# Power_Distribution_V1_1.net
KiCad netlist of a schematic drawn in EAGLE
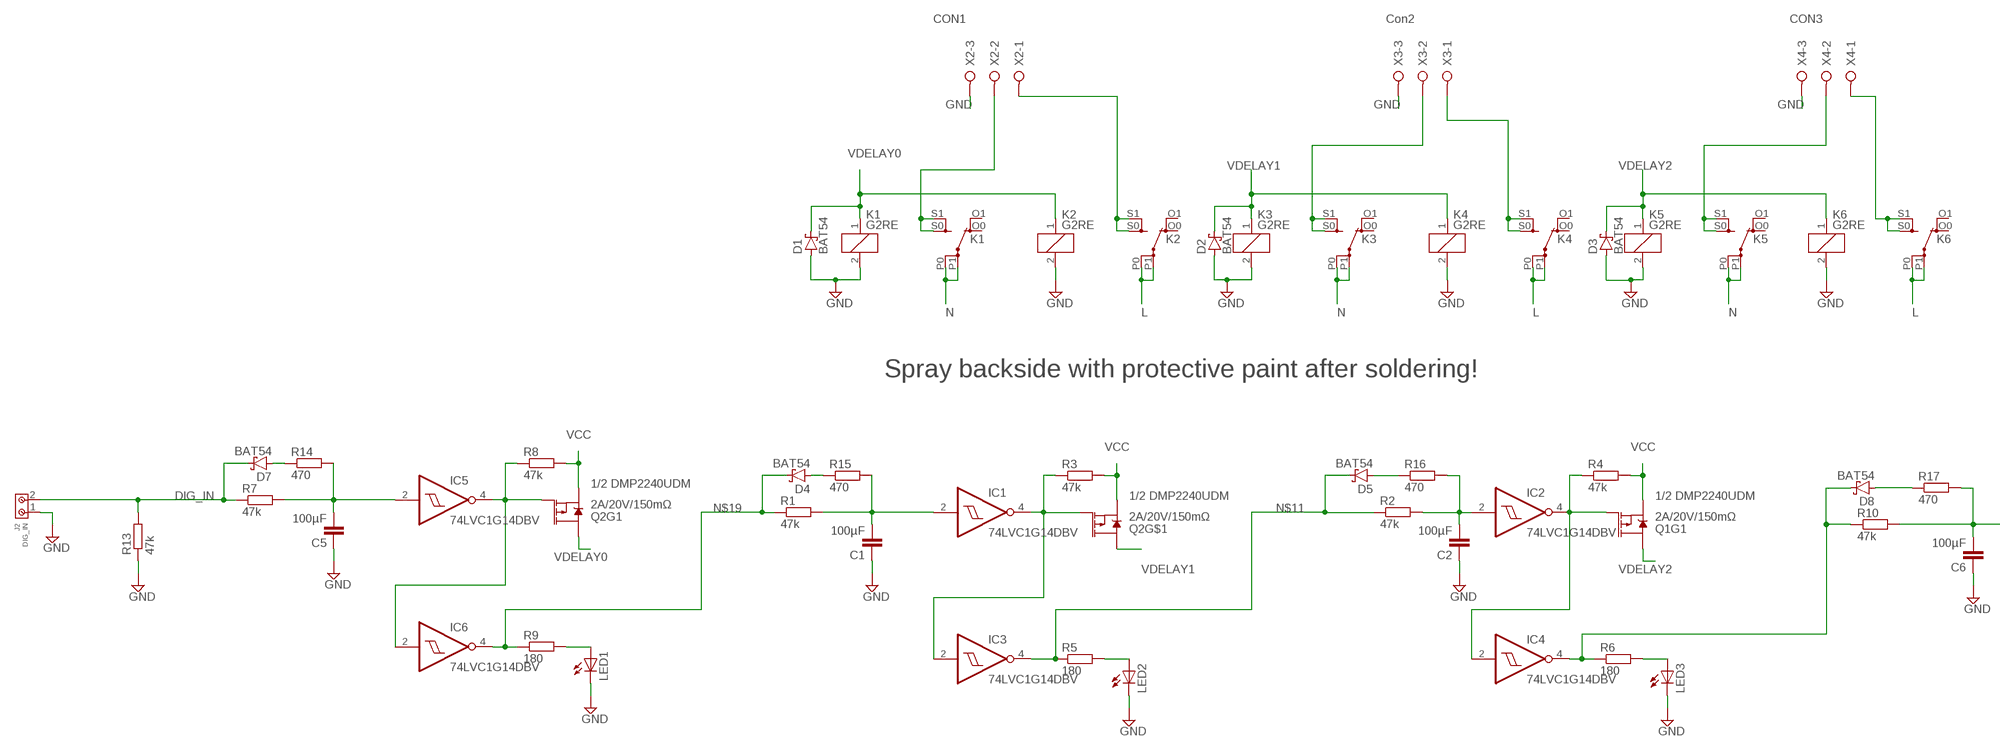
[diagram p0: schematic, sheet 1, part 1 of 2]
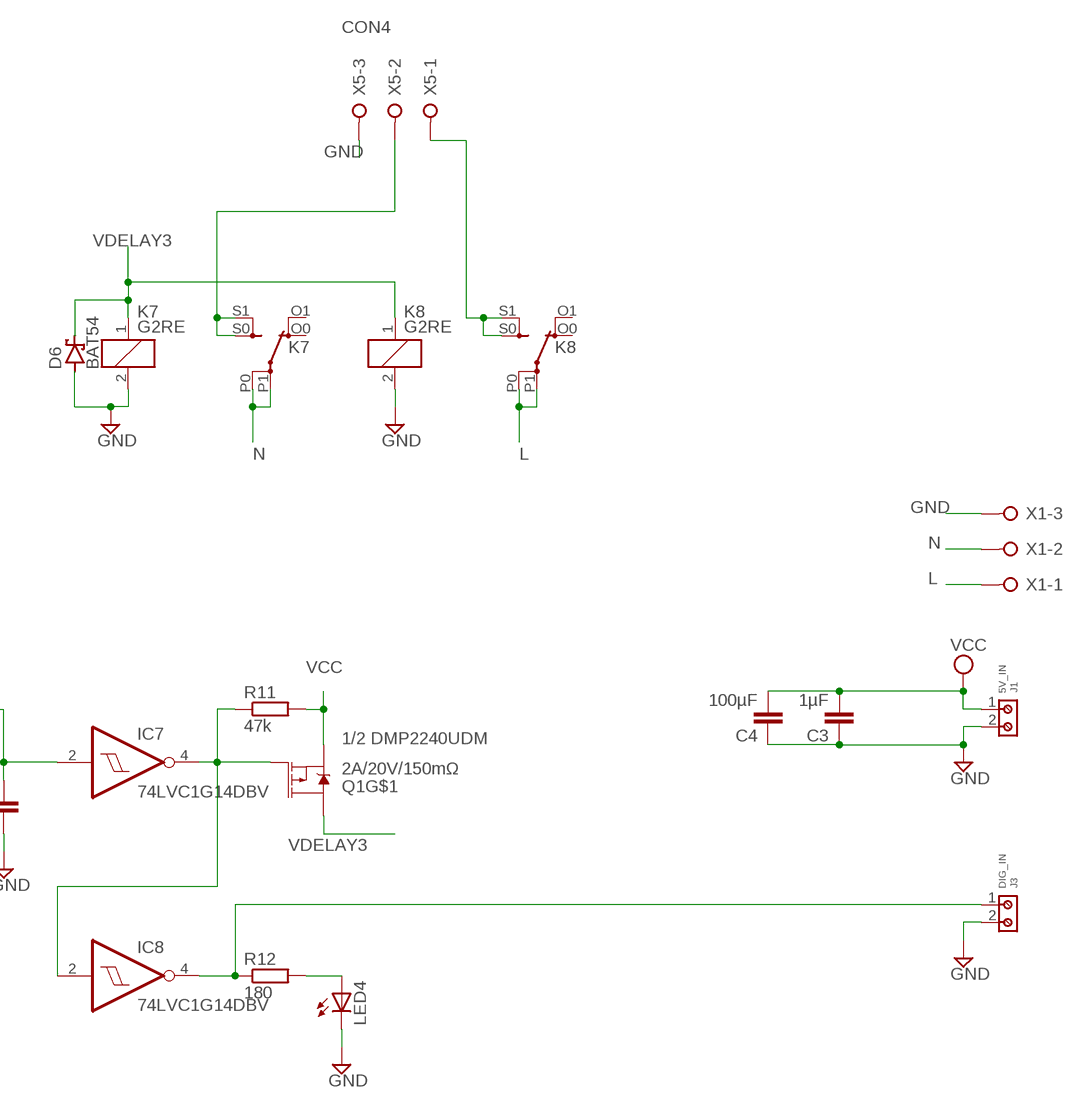
[diagram p1: schematic, sheet 1, part 2 of 2]

(export (version "E")
  (design (tool "Eeschema 10.0.6"))
  (components
    (comp (ref "C1")
      (value "100µF")
      (footprint "eagle-import:C1210")
      (libsource (lib "eagle-import") (part "C-EUC1210"))
    )
    (comp (ref "C2")
      (value "100µF")
      (footprint "eagle-import:C1210")
      (libsource (lib "eagle-import") (part "C-EUC1210"))
    )
    (comp (ref "C3")
      (value "1µF")
      (footprint "eagle-import:C1210")
      (libsource (lib "eagle-import") (part "C-EUC1210"))
    )
    (comp (ref "C4")
      (value "100µF")
      (footprint "eagle-import:C1210")
      (libsource (lib "eagle-import") (part "C-EUC1210"))
    )
    (comp (ref "C5")
      (value "100µF")
      (footprint "eagle-import:C1210")
      (libsource (lib "eagle-import") (part "C-EUC1210"))
    )
    (comp (ref "C6")
      (value "100µF")
      (footprint "eagle-import:C1210")
      (libsource (lib "eagle-import") (part "C-EUC1210"))
    )
    (comp (ref "D1")
      (value "BAT54")
      (footprint "eagle-import:SOT23")
      (libsource (lib "eagle-import") (part "BAT54"))
    )
    (comp (ref "D2")
      (value "BAT54")
      (footprint "eagle-import:SOT23")
      (libsource (lib "eagle-import") (part "BAT54"))
    )
    (comp (ref "D3")
      (value "BAT54")
      (footprint "eagle-import:SOT23")
      (libsource (lib "eagle-import") (part "BAT54"))
    )
    (comp (ref "D4")
      (value "BAT54")
      (footprint "eagle-import:SOT23")
      (libsource (lib "eagle-import") (part "BAT54"))
    )
    (comp (ref "D5")
      (value "BAT54")
      (footprint "eagle-import:SOT23")
      (libsource (lib "eagle-import") (part "BAT54"))
    )
    (comp (ref "D6")
      (value "BAT54")
      (footprint "eagle-import:SOT23")
      (libsource (lib "eagle-import") (part "BAT54"))
    )
    (comp (ref "D7")
      (value "BAT54")
      (footprint "eagle-import:SOT23")
      (libsource (lib "eagle-import") (part "BAT54"))
    )
    (comp (ref "D8")
      (value "BAT54")
      (footprint "eagle-import:SOT23")
      (libsource (lib "eagle-import") (part "BAT54"))
    )
    (comp (ref "IC1")
      (value "74LVC1G14DBV")
      (footprint "eagle-import:SOT23-5")
      (libsource (lib "eagle-import") (part "741G14DBVLVC"))
    )
    (comp (ref "IC2")
      (value "74LVC1G14DBV")
      (footprint "eagle-import:SOT23-5")
      (libsource (lib "eagle-import") (part "741G14DBVLVC"))
    )
    (comp (ref "IC3")
      (value "74LVC1G14DBV")
      (footprint "eagle-import:SOT23-5")
      (libsource (lib "eagle-import") (part "741G14DBVLVC"))
    )
    (comp (ref "IC4")
      (value "74LVC1G14DBV")
      (footprint "eagle-import:SOT23-5")
      (libsource (lib "eagle-import") (part "741G14DBVLVC"))
    )
    (comp (ref "IC5")
      (value "74LVC1G14DBV")
      (footprint "eagle-import:SOT23-5")
      (libsource (lib "eagle-import") (part "741G14DBVLVC"))
    )
    (comp (ref "IC6")
      (value "74LVC1G14DBV")
      (footprint "eagle-import:SOT23-5")
      (libsource (lib "eagle-import") (part "741G14DBVLVC"))
    )
    (comp (ref "IC7")
      (value "74LVC1G14DBV")
      (footprint "eagle-import:SOT23-5")
      (libsource (lib "eagle-import") (part "741G14DBVLVC"))
    )
    (comp (ref "IC8")
      (value "74LVC1G14DBV")
      (footprint "eagle-import:SOT23-5")
      (libsource (lib "eagle-import") (part "741G14DBVLVC"))
    )
    (comp (ref "J1")
      (value "5V_IN")
      (footprint "eagle-import:691210910002")
      (libsource (lib "eagle-import") (part "691210910002"))
    )
    (comp (ref "J2")
      (value "DIG_IN")
      (footprint "eagle-import:691210910002")
      (libsource (lib "eagle-import") (part "691210910002"))
    )
    (comp (ref "J3")
      (value "DIG_IN")
      (footprint "eagle-import:691210910002")
      (libsource (lib "eagle-import") (part "691210910002"))
    )
    (comp (ref "K1")
      (value "G2RE")
      (footprint "eagle-import:G2RE")
      (libsource (lib "eagle-import") (part "G2RE"))
    )
    (comp (ref "K2")
      (value "G2RE")
      (footprint "eagle-import:G2RE")
      (libsource (lib "eagle-import") (part "G2RE"))
    )
    (comp (ref "K3")
      (value "G2RE")
      (footprint "eagle-import:G2RE")
      (libsource (lib "eagle-import") (part "G2RE"))
    )
    (comp (ref "K4")
      (value "G2RE")
      (footprint "eagle-import:G2RE")
      (libsource (lib "eagle-import") (part "G2RE"))
    )
    (comp (ref "K5")
      (value "G2RE")
      (footprint "eagle-import:G2RE")
      (libsource (lib "eagle-import") (part "G2RE"))
    )
    (comp (ref "K6")
      (value "G2RE")
      (footprint "eagle-import:G2RE")
      (libsource (lib "eagle-import") (part "G2RE"))
    )
    (comp (ref "K7")
      (value "G2RE")
      (footprint "eagle-import:G2RE")
      (libsource (lib "eagle-import") (part "G2RE"))
    )
    (comp (ref "K8")
      (value "G2RE")
      (footprint "eagle-import:G2RE")
      (libsource (lib "eagle-import") (part "G2RE"))
    )
    (comp (ref "LED1")
      (value "LED3MM")
      (footprint "eagle-import:LED3MM")
      (libsource (lib "eagle-import") (part "LED3MM"))
    )
    (comp (ref "LED2")
      (value "LED3MM")
      (footprint "eagle-import:LED3MM")
      (libsource (lib "eagle-import") (part "LED3MM"))
    )
    (comp (ref "LED3")
      (value "LED3MM")
      (footprint "eagle-import:LED3MM")
      (libsource (lib "eagle-import") (part "LED3MM"))
    )
    (comp (ref "LED4")
      (value "LED3MM")
      (footprint "eagle-import:LED3MM")
      (libsource (lib "eagle-import") (part "LED3MM"))
    )
    (comp (ref "Q1")
      (value "2A/20V/150mΩ")
      (footprint "eagle-import:SOT26")
      (libsource (lib "eagle-import") (part "MOSFET_PCH_DUAL-DMP2240UDM"))
    )
    (comp (ref "Q2")
      (value "2A/20V/150mΩ")
      (footprint "eagle-import:SOT26")
      (libsource (lib "eagle-import") (part "MOSFET_PCH_DUAL-DMP2240UDM"))
    )
    (comp (ref "R1")
      (value "47k")
      (footprint "eagle-import:R0805")
      (libsource (lib "eagle-import") (part "R-EU_R0805"))
    )
    (comp (ref "R2")
      (value "47k")
      (footprint "eagle-import:R0805")
      (libsource (lib "eagle-import") (part "R-EU_R0805"))
    )
    (comp (ref "R3")
      (value "47k")
      (footprint "eagle-import:R0805")
      (libsource (lib "eagle-import") (part "R-EU_R0805"))
    )
    (comp (ref "R4")
      (value "47k")
      (footprint "eagle-import:R0805")
      (libsource (lib "eagle-import") (part "R-EU_R0805"))
    )
    (comp (ref "R5")
      (value "180")
      (footprint "eagle-import:R0805")
      (libsource (lib "eagle-import") (part "R-EU_R0805"))
    )
    (comp (ref "R6")
      (value "180")
      (footprint "eagle-import:R0805")
      (libsource (lib "eagle-import") (part "R-EU_R0805"))
    )
    (comp (ref "R7")
      (value "47k")
      (footprint "eagle-import:R0805")
      (libsource (lib "eagle-import") (part "R-EU_R0805"))
    )
    (comp (ref "R8")
      (value "47k")
      (footprint "eagle-import:R0805")
      (libsource (lib "eagle-import") (part "R-EU_R0805"))
    )
    (comp (ref "R9")
      (value "180")
      (footprint "eagle-import:R0805")
      (libsource (lib "eagle-import") (part "R-EU_R0805"))
    )
    (comp (ref "R10")
      (value "47k")
      (footprint "eagle-import:R0805")
      (libsource (lib "eagle-import") (part "R-EU_R0805"))
    )
    (comp (ref "R11")
      (value "47k")
      (footprint "eagle-import:R0805")
      (libsource (lib "eagle-import") (part "R-EU_R0805"))
    )
    (comp (ref "R12")
      (value "180")
      (footprint "eagle-import:R0805")
      (libsource (lib "eagle-import") (part "R-EU_R0805"))
    )
    (comp (ref "R13")
      (value "47k")
      (footprint "eagle-import:R0805")
      (libsource (lib "eagle-import") (part "R-EU_R0805"))
    )
    (comp (ref "R14")
      (value "470")
      (footprint "eagle-import:R0805")
      (libsource (lib "eagle-import") (part "R-EU_R0805"))
    )
    (comp (ref "R15")
      (value "470")
      (footprint "eagle-import:R0805")
      (libsource (lib "eagle-import") (part "R-EU_R0805"))
    )
    (comp (ref "R16")
      (value "470")
      (footprint "eagle-import:R0805")
      (libsource (lib "eagle-import") (part "R-EU_R0805"))
    )
    (comp (ref "R17")
      (value "470")
      (footprint "eagle-import:R0805")
      (libsource (lib "eagle-import") (part "R-EU_R0805"))
    )
    (comp (ref "X1")
      (value "W237-3E")
      (footprint "eagle-import:W237-3E")
      (libsource (lib "eagle-import") (part "W237-3E"))
    )
    (comp (ref "X2")
      (value "W237-3E")
      (footprint "eagle-import:W237-3E")
      (libsource (lib "eagle-import") (part "W237-3E"))
    )
    (comp (ref "X3")
      (value "W237-3E")
      (footprint "eagle-import:W237-3E")
      (libsource (lib "eagle-import") (part "W237-3E"))
    )
    (comp (ref "X4")
      (value "W237-3E")
      (footprint "eagle-import:W237-3E")
      (libsource (lib "eagle-import") (part "W237-3E"))
    )
    (comp (ref "X5")
      (value "W237-3E")
      (footprint "eagle-import:W237-3E")
      (libsource (lib "eagle-import") (part "W237-3E"))
    )
  )
  (nets
    (net (code "1") (name "/DIG_IN") (class "Default")
      (node (ref "D7") (pin "3") (pinfunction "C_3") (pintype "passive"))
      (node (ref "J2") (pin "2") (pinfunction "2_2") (pintype "passive"))
      (node (ref "R13") (pin "2") (pinfunction "2_2") (pintype "passive"))
      (node (ref "R7") (pin "1") (pinfunction "1_1") (pintype "passive"))
    )
    (net (code "2") (name "/L") (class "Default")
      (node (ref "K2") (pin "P0") (pinfunction "P_P0") (pintype "passive"))
      (node (ref "K2") (pin "P1") (pinfunction "P_P1") (pintype "passive"))
      (node (ref "K4") (pin "P0") (pinfunction "P_P0") (pintype "passive"))
      (node (ref "K4") (pin "P1") (pinfunction "P_P1") (pintype "passive"))
      (node (ref "K6") (pin "P0") (pinfunction "P_P0") (pintype "passive"))
      (node (ref "K6") (pin "P1") (pinfunction "P_P1") (pintype "passive"))
      (node (ref "K8") (pin "P0") (pinfunction "P_P0") (pintype "passive"))
      (node (ref "K8") (pin "P1") (pinfunction "P_P1") (pintype "passive"))
      (node (ref "X1") (pin "1") (pinfunction "KL_1") (pintype "passive"))
    )
    (net (code "3") (name "/N") (class "Default")
      (node (ref "K1") (pin "P0") (pinfunction "P_P0") (pintype "passive"))
      (node (ref "K1") (pin "P1") (pinfunction "P_P1") (pintype "passive"))
      (node (ref "K3") (pin "P0") (pinfunction "P_P0") (pintype "passive"))
      (node (ref "K3") (pin "P1") (pinfunction "P_P1") (pintype "passive"))
      (node (ref "K5") (pin "P0") (pinfunction "P_P0") (pintype "passive"))
      (node (ref "K5") (pin "P1") (pinfunction "P_P1") (pintype "passive"))
      (node (ref "K7") (pin "P0") (pinfunction "P_P0") (pintype "passive"))
      (node (ref "K7") (pin "P1") (pinfunction "P_P1") (pintype "passive"))
      (node (ref "X1") (pin "2") (pinfunction "KL_2") (pintype "passive"))
    )
    (net (code "4") (name "/N$11") (class "Default")
      (node (ref "D5") (pin "3") (pinfunction "C_3") (pintype "passive"))
      (node (ref "IC3") (pin "4") (pinfunction "O_4") (pintype "output"))
      (node (ref "R2") (pin "1") (pinfunction "1_1") (pintype "passive"))
      (node (ref "R5") (pin "1") (pinfunction "1_1") (pintype "passive"))
    )
    (net (code "5") (name "/N$19") (class "Default")
      (node (ref "D4") (pin "3") (pinfunction "C_3") (pintype "passive"))
      (node (ref "IC6") (pin "4") (pinfunction "O_4") (pintype "output"))
      (node (ref "R1") (pin "1") (pinfunction "1_1") (pintype "passive"))
      (node (ref "R9") (pin "1") (pinfunction "1_1") (pintype "passive"))
    )
    (net (code "6") (name "/VDELAY0") (class "Default")
      (node (ref "D1") (pin "3") (pinfunction "C_3") (pintype "passive"))
      (node (ref "K1") (pin "1") (pinfunction "1_1") (pintype "passive"))
      (node (ref "K2") (pin "1") (pinfunction "1_1") (pintype "passive"))
      (node (ref "Q2") (pin "D1") (pinfunction "D_D1") (pintype "bidirectional"))
    )
    (net (code "7") (name "/VDELAY1") (class "Default")
      (node (ref "D2") (pin "3") (pinfunction "C_3") (pintype "passive"))
      (node (ref "K3") (pin "1") (pinfunction "1_1") (pintype "passive"))
      (node (ref "K4") (pin "1") (pinfunction "1_1") (pintype "passive"))
      (node (ref "Q2") (pin "D2") (pinfunction "D_D2") (pintype "bidirectional"))
    )
    (net (code "8") (name "/VDELAY2") (class "Default")
      (node (ref "D3") (pin "3") (pinfunction "C_3") (pintype "passive"))
      (node (ref "K5") (pin "1") (pinfunction "1_1") (pintype "passive"))
      (node (ref "K6") (pin "1") (pinfunction "1_1") (pintype "passive"))
      (node (ref "Q1") (pin "D1") (pinfunction "D_D1") (pintype "bidirectional"))
    )
    (net (code "9") (name "/VDELAY3") (class "Default")
      (node (ref "D6") (pin "3") (pinfunction "C_3") (pintype "passive"))
      (node (ref "K7") (pin "1") (pinfunction "1_1") (pintype "passive"))
      (node (ref "K8") (pin "1") (pinfunction "1_1") (pintype "passive"))
      (node (ref "Q1") (pin "D2") (pinfunction "D_D2") (pintype "bidirectional"))
    )
    (net (code "10") (name "GND") (class "Default")
      (node (ref "C1") (pin "1") (pinfunction "1_1") (pintype "passive"))
      (node (ref "C2") (pin "1") (pinfunction "1_1") (pintype "passive"))
      (node (ref "C3") (pin "1") (pinfunction "1_1") (pintype "passive"))
      (node (ref "C4") (pin "1") (pinfunction "1_1") (pintype "passive"))
      (node (ref "C5") (pin "1") (pinfunction "1_1") (pintype "passive"))
      (node (ref "C6") (pin "1") (pinfunction "1_1") (pintype "passive"))
      (node (ref "D1") (pin "1") (pinfunction "A_1") (pintype "passive"))
      (node (ref "D2") (pin "1") (pinfunction "A_1") (pintype "passive"))
      (node (ref "D3") (pin "1") (pinfunction "A_1") (pintype "passive"))
      (node (ref "D6") (pin "1") (pinfunction "A_1") (pintype "passive"))
      (node (ref "J1") (pin "2") (pinfunction "2_2") (pintype "passive"))
      (node (ref "J2") (pin "1") (pinfunction "1_1") (pintype "passive"))
      (node (ref "J3") (pin "2") (pinfunction "2_2") (pintype "passive"))
      (node (ref "K1") (pin "2") (pinfunction "2_2") (pintype "passive"))
      (node (ref "K2") (pin "2") (pinfunction "2_2") (pintype "passive"))
      (node (ref "K3") (pin "2") (pinfunction "2_2") (pintype "passive"))
      (node (ref "K4") (pin "2") (pinfunction "2_2") (pintype "passive"))
      (node (ref "K5") (pin "2") (pinfunction "2_2") (pintype "passive"))
      (node (ref "K6") (pin "2") (pinfunction "2_2") (pintype "passive"))
      (node (ref "K7") (pin "2") (pinfunction "2_2") (pintype "passive"))
      (node (ref "K8") (pin "2") (pinfunction "2_2") (pintype "passive"))
      (node (ref "LED1") (pin "K") (pinfunction "C_K") (pintype "passive"))
      (node (ref "LED2") (pin "K") (pinfunction "C_K") (pintype "passive"))
      (node (ref "LED3") (pin "K") (pinfunction "C_K") (pintype "passive"))
      (node (ref "LED4") (pin "K") (pinfunction "C_K") (pintype "passive"))
      (node (ref "R13") (pin "1") (pinfunction "1_1") (pintype "passive"))
      (node (ref "X1") (pin "3") (pinfunction "KL_3") (pintype "passive"))
      (node (ref "X2") (pin "3") (pinfunction "KL_3") (pintype "passive"))
      (node (ref "X3") (pin "3") (pinfunction "KL_3") (pintype "passive"))
      (node (ref "X4") (pin "3") (pinfunction "KL_3") (pintype "passive"))
      (node (ref "X5") (pin "3") (pinfunction "KL_3") (pintype "passive"))
    )
    (net (code "11") (name "Net-(D4-A)") (class "Default")
      (node (ref "D4") (pin "1") (pinfunction "A_1") (pintype "passive"))
      (node (ref "R15") (pin "1") (pinfunction "1_1") (pintype "passive"))
    )
    (net (code "12") (name "Net-(D5-A)") (class "Default")
      (node (ref "D5") (pin "1") (pinfunction "A_1") (pintype "passive"))
      (node (ref "R16") (pin "1") (pinfunction "1_1") (pintype "passive"))
    )
    (net (code "13") (name "Net-(D7-A)") (class "Default")
      (node (ref "D7") (pin "1") (pinfunction "A_1") (pintype "passive"))
      (node (ref "R14") (pin "1") (pinfunction "1_1") (pintype "passive"))
    )
    (net (code "14") (name "Net-(D8-A)") (class "Default")
      (node (ref "D8") (pin "1") (pinfunction "A_1") (pintype "passive"))
      (node (ref "R17") (pin "1") (pinfunction "1_1") (pintype "passive"))
    )
    (net (code "15") (name "Net-(D8-C)") (class "Default")
      (node (ref "D8") (pin "3") (pinfunction "C_3") (pintype "passive"))
      (node (ref "IC4") (pin "4") (pinfunction "O_4") (pintype "output"))
      (node (ref "R10") (pin "1") (pinfunction "1_1") (pintype "passive"))
      (node (ref "R6") (pin "1") (pinfunction "1_1") (pintype "passive"))
    )
    (net (code "16") (name "Net-(IC1A-I)") (class "Default")
      (node (ref "C1") (pin "2") (pinfunction "2_2") (pintype "passive"))
      (node (ref "IC1") (pin "2") (pinfunction "I_2") (pintype "input"))
      (node (ref "R1") (pin "2") (pinfunction "2_2") (pintype "passive"))
      (node (ref "R15") (pin "2") (pinfunction "2_2") (pintype "passive"))
    )
    (net (code "17") (name "Net-(IC1A-O)") (class "Default")
      (node (ref "IC1") (pin "4") (pinfunction "O_4") (pintype "output"))
      (node (ref "IC3") (pin "2") (pinfunction "I_2") (pintype "input"))
      (node (ref "Q2") (pin "G2") (pinfunction "G_G2") (pintype "bidirectional"))
      (node (ref "R3") (pin "1") (pinfunction "1_1") (pintype "passive"))
    )
    (net (code "18") (name "Net-(IC2A-I)") (class "Default")
      (node (ref "C2") (pin "2") (pinfunction "2_2") (pintype "passive"))
      (node (ref "IC2") (pin "2") (pinfunction "I_2") (pintype "input"))
      (node (ref "R16") (pin "2") (pinfunction "2_2") (pintype "passive"))
      (node (ref "R2") (pin "2") (pinfunction "2_2") (pintype "passive"))
    )
    (net (code "19") (name "Net-(IC2A-O)") (class "Default")
      (node (ref "IC2") (pin "4") (pinfunction "O_4") (pintype "output"))
      (node (ref "IC4") (pin "2") (pinfunction "I_2") (pintype "input"))
      (node (ref "Q1") (pin "G1") (pinfunction "G_G1") (pintype "bidirectional"))
      (node (ref "R4") (pin "1") (pinfunction "1_1") (pintype "passive"))
    )
    (net (code "20") (name "Net-(IC5A-I)") (class "Default")
      (node (ref "C5") (pin "2") (pinfunction "2_2") (pintype "passive"))
      (node (ref "IC5") (pin "2") (pinfunction "I_2") (pintype "input"))
      (node (ref "R14") (pin "2") (pinfunction "2_2") (pintype "passive"))
      (node (ref "R7") (pin "2") (pinfunction "2_2") (pintype "passive"))
    )
    (net (code "21") (name "Net-(IC5A-O)") (class "Default")
      (node (ref "IC5") (pin "4") (pinfunction "O_4") (pintype "output"))
      (node (ref "IC6") (pin "2") (pinfunction "I_2") (pintype "input"))
      (node (ref "Q2") (pin "G1") (pinfunction "G_G1") (pintype "bidirectional"))
      (node (ref "R8") (pin "1") (pinfunction "1_1") (pintype "passive"))
    )
    (net (code "22") (name "Net-(IC7A-I)") (class "Default")
      (node (ref "C6") (pin "2") (pinfunction "2_2") (pintype "passive"))
      (node (ref "IC7") (pin "2") (pinfunction "I_2") (pintype "input"))
      (node (ref "R10") (pin "2") (pinfunction "2_2") (pintype "passive"))
      (node (ref "R17") (pin "2") (pinfunction "2_2") (pintype "passive"))
    )
    (net (code "23") (name "Net-(IC7A-O)") (class "Default")
      (node (ref "IC7") (pin "4") (pinfunction "O_4") (pintype "output"))
      (node (ref "IC8") (pin "2") (pinfunction "I_2") (pintype "input"))
      (node (ref "Q1") (pin "G2") (pinfunction "G_G2") (pintype "bidirectional"))
      (node (ref "R11") (pin "1") (pinfunction "1_1") (pintype "passive"))
    )
    (net (code "24") (name "Net-(IC8A-O)") (class "Default")
      (node (ref "IC8") (pin "4") (pinfunction "O_4") (pintype "output"))
      (node (ref "J3") (pin "1") (pinfunction "1_1") (pintype "passive"))
      (node (ref "R12") (pin "1") (pinfunction "1_1") (pintype "passive"))
    )
    (net (code "25") (name "Net-(LED1-PadA)") (class "Default")
      (node (ref "LED1") (pin "A") (pinfunction "A_A") (pintype "passive"))
      (node (ref "R9") (pin "2") (pinfunction "2_2") (pintype "passive"))
    )
    (net (code "26") (name "Net-(LED2-PadA)") (class "Default")
      (node (ref "LED2") (pin "A") (pinfunction "A_A") (pintype "passive"))
      (node (ref "R5") (pin "2") (pinfunction "2_2") (pintype "passive"))
    )
    (net (code "27") (name "Net-(LED3-PadA)") (class "Default")
      (node (ref "LED3") (pin "A") (pinfunction "A_A") (pintype "passive"))
      (node (ref "R6") (pin "2") (pinfunction "2_2") (pintype "passive"))
    )
    (net (code "28") (name "Net-(LED4-PadA)") (class "Default")
      (node (ref "LED4") (pin "A") (pinfunction "A_A") (pintype "passive"))
      (node (ref "R12") (pin "2") (pinfunction "2_2") (pintype "passive"))
    )
    (net (code "29") (name "Net-(X2A-KL)") (class "Default")
      (node (ref "K2") (pin "S0") (pinfunction "S_S0") (pintype "passive"))
      (node (ref "K2") (pin "S1") (pinfunction "S_S1") (pintype "passive"))
      (node (ref "X2") (pin "1") (pinfunction "KL_1") (pintype "passive"))
    )
    (net (code "30") (name "Net-(X2B-KL)") (class "Default")
      (node (ref "K1") (pin "S0") (pinfunction "S_S0") (pintype "passive"))
      (node (ref "K1") (pin "S1") (pinfunction "S_S1") (pintype "passive"))
      (node (ref "X2") (pin "2") (pinfunction "KL_2") (pintype "passive"))
    )
    (net (code "31") (name "Net-(X3A-KL)") (class "Default")
      (node (ref "K4") (pin "S0") (pinfunction "S_S0") (pintype "passive"))
      (node (ref "K4") (pin "S1") (pinfunction "S_S1") (pintype "passive"))
      (node (ref "X3") (pin "1") (pinfunction "KL_1") (pintype "passive"))
    )
    (net (code "32") (name "Net-(X3B-KL)") (class "Default")
      (node (ref "K3") (pin "S0") (pinfunction "S_S0") (pintype "passive"))
      (node (ref "K3") (pin "S1") (pinfunction "S_S1") (pintype "passive"))
      (node (ref "X3") (pin "2") (pinfunction "KL_2") (pintype "passive"))
    )
    (net (code "33") (name "Net-(X4A-KL)") (class "Default")
      (node (ref "K6") (pin "S0") (pinfunction "S_S0") (pintype "passive"))
      (node (ref "K6") (pin "S1") (pinfunction "S_S1") (pintype "passive"))
      (node (ref "X4") (pin "1") (pinfunction "KL_1") (pintype "passive"))
    )
    (net (code "34") (name "Net-(X4B-KL)") (class "Default")
      (node (ref "K5") (pin "S0") (pinfunction "S_S0") (pintype "passive"))
      (node (ref "K5") (pin "S1") (pinfunction "S_S1") (pintype "passive"))
      (node (ref "X4") (pin "2") (pinfunction "KL_2") (pintype "passive"))
    )
    (net (code "35") (name "Net-(X5A-KL)") (class "Default")
      (node (ref "K8") (pin "S0") (pinfunction "S_S0") (pintype "passive"))
      (node (ref "K8") (pin "S1") (pinfunction "S_S1") (pintype "passive"))
      (node (ref "X5") (pin "1") (pinfunction "KL_1") (pintype "passive"))
    )
    (net (code "36") (name "Net-(X5B-KL)") (class "Default")
      (node (ref "K7") (pin "S0") (pinfunction "S_S0") (pintype "passive"))
      (node (ref "K7") (pin "S1") (pinfunction "S_S1") (pintype "passive"))
      (node (ref "X5") (pin "2") (pinfunction "KL_2") (pintype "passive"))
    )
    (net (code "37") (name "VCC") (class "Default")
      (node (ref "C3") (pin "2") (pinfunction "2_2") (pintype "passive"))
      (node (ref "C4") (pin "2") (pinfunction "2_2") (pintype "passive"))
      (node (ref "J1") (pin "1") (pinfunction "1_1") (pintype "passive"))
      (node (ref "Q1") (pin "S1") (pinfunction "S_S1") (pintype "bidirectional"))
      (node (ref "Q1") (pin "S2") (pinfunction "S_S2") (pintype "bidirectional"))
      (node (ref "Q2") (pin "S1") (pinfunction "S_S1") (pintype "bidirectional"))
      (node (ref "Q2") (pin "S2") (pinfunction "S_S2") (pintype "bidirectional"))
      (node (ref "R11") (pin "2") (pinfunction "2_2") (pintype "passive"))
      (node (ref "R3") (pin "2") (pinfunction "2_2") (pintype "passive"))
      (node (ref "R4") (pin "2") (pinfunction "2_2") (pintype "passive"))
      (node (ref "R8") (pin "2") (pinfunction "2_2") (pintype "passive"))
    )
    (net (code "38") (name "unconnected-(K1B-O-PadO0)") (class "Default")
      (node (ref "K1") (pin "O0") (pinfunction "O_O0") (pintype "passive"))
    )
    (net (code "39") (name "unconnected-(K1B-O-PadO1)") (class "Default")
      (node (ref "K1") (pin "O1") (pinfunction "O_O1") (pintype "passive"))
    )
    (net (code "40") (name "unconnected-(K2B-O-PadO0)") (class "Default")
      (node (ref "K2") (pin "O0") (pinfunction "O_O0") (pintype "passive"))
    )
    (net (code "41") (name "unconnected-(K2B-O-PadO1)") (class "Default")
      (node (ref "K2") (pin "O1") (pinfunction "O_O1") (pintype "passive"))
    )
    (net (code "42") (name "unconnected-(K3B-O-PadO0)") (class "Default")
      (node (ref "K3") (pin "O0") (pinfunction "O_O0") (pintype "passive"))
    )
    (net (code "43") (name "unconnected-(K3B-O-PadO1)") (class "Default")
      (node (ref "K3") (pin "O1") (pinfunction "O_O1") (pintype "passive"))
    )
    (net (code "44") (name "unconnected-(K4B-O-PadO0)") (class "Default")
      (node (ref "K4") (pin "O0") (pinfunction "O_O0") (pintype "passive"))
    )
    (net (code "45") (name "unconnected-(K4B-O-PadO1)") (class "Default")
      (node (ref "K4") (pin "O1") (pinfunction "O_O1") (pintype "passive"))
    )
    (net (code "46") (name "unconnected-(K5B-O-PadO0)") (class "Default")
      (node (ref "K5") (pin "O0") (pinfunction "O_O0") (pintype "passive"))
    )
    (net (code "47") (name "unconnected-(K5B-O-PadO1)") (class "Default")
      (node (ref "K5") (pin "O1") (pinfunction "O_O1") (pintype "passive"))
    )
    (net (code "48") (name "unconnected-(K6B-O-PadO0)") (class "Default")
      (node (ref "K6") (pin "O0") (pinfunction "O_O0") (pintype "passive"))
    )
    (net (code "49") (name "unconnected-(K6B-O-PadO1)") (class "Default")
      (node (ref "K6") (pin "O1") (pinfunction "O_O1") (pintype "passive"))
    )
    (net (code "50") (name "unconnected-(K7B-O-PadO0)") (class "Default")
      (node (ref "K7") (pin "O0") (pinfunction "O_O0") (pintype "passive"))
    )
    (net (code "51") (name "unconnected-(K7B-O-PadO1)") (class "Default")
      (node (ref "K7") (pin "O1") (pinfunction "O_O1") (pintype "passive"))
    )
    (net (code "52") (name "unconnected-(K8B-O-PadO0)") (class "Default")
      (node (ref "K8") (pin "O0") (pinfunction "O_O0") (pintype "passive"))
    )
    (net (code "53") (name "unconnected-(K8B-O-PadO1)") (class "Default")
      (node (ref "K8") (pin "O1") (pinfunction "O_O1") (pintype "passive"))
    )
  )
)
